# LoRaGN.net
KiCad netlist of a schematic drawn in Altium Designer
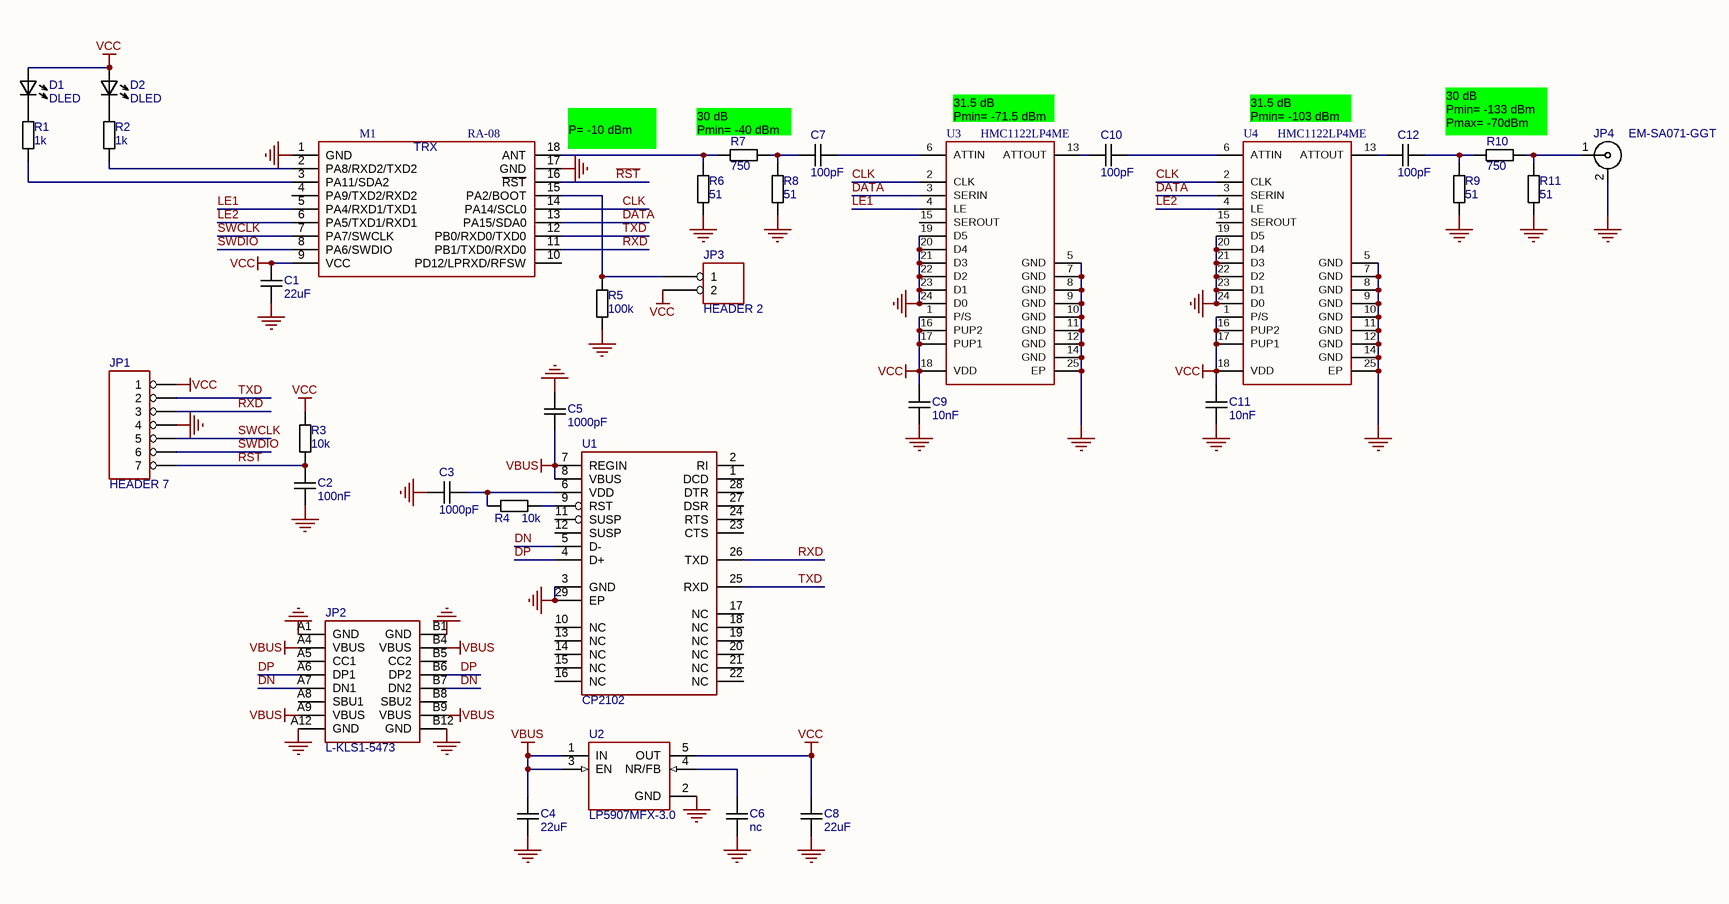
[diagram p0: LoRaGN.SchDoc]

(export (version "E")
  (design (tool "Eeschema 10.0.6"))
  (components
    (comp (ref "C1")
      (value "22uF")
      (footprint "C-0805")
      (fields (field (name "VOLTAGE") "50V"))
      (libsource (lib "Passive") (part "CAPN"))
    )
    (comp (ref "C2")
      (value "100nF")
      (footprint "C-0603")
      (fields (field (name "VOLTAGE") "50V"))
      (libsource (lib "Passive") (part "CAPN"))
    )
    (comp (ref "C3")
      (value "1000pF")
      (footprint "C-0603")
      (fields (field (name "VOLTAGE") "50V"))
      (libsource (lib "Passive") (part "CAPN"))
    )
    (comp (ref "C4")
      (value "22uF")
      (footprint "C-0805")
      (fields (field (name "VOLTAGE") "50V"))
      (libsource (lib "Passive") (part "CAPN"))
    )
    (comp (ref "C5")
      (value "1000pF")
      (footprint "C-0603")
      (fields (field (name "VOLTAGE") "50V"))
      (libsource (lib "Passive") (part "CAPN"))
    )
    (comp (ref "C6")
      (value "nc")
      (footprint "C-0603")
      (fields (field (name "VOLTAGE") "50V"))
      (libsource (lib "Passive") (part "CAPN"))
    )
    (comp (ref "C7")
      (value "100pF")
      (footprint "C-0603")
      (fields (field (name "VOLTAGE") "50V"))
      (libsource (lib "Passive") (part "CAPN"))
    )
    (comp (ref "C8")
      (value "22uF")
      (footprint "C-0805")
      (fields (field (name "VOLTAGE") "50V"))
      (libsource (lib "Passive") (part "CAPN"))
    )
    (comp (ref "C9")
      (value "10nF")
      (footprint "C-0603")
      (fields (field (name "VOLTAGE") "50V"))
      (libsource (lib "Passive") (part "CAPN"))
    )
    (comp (ref "C10")
      (value "100pF")
      (footprint "C-0603")
      (fields (field (name "VOLTAGE") "50V"))
      (libsource (lib "Passive") (part "CAPN"))
    )
    (comp (ref "C11")
      (value "10nF")
      (footprint "C-0603")
      (fields (field (name "VOLTAGE") "50V"))
      (libsource (lib "Passive") (part "CAPN"))
    )
    (comp (ref "C12")
      (value "100pF")
      (footprint "C-0603")
      (fields (field (name "VOLTAGE") "50V"))
      (libsource (lib "Passive") (part "CAPN"))
    )
    (comp (ref "D1") (value "DLED") (footprint "LED0805") (libsource (lib "Diodes") (part "DLED")))
    (comp (ref "D2") (value "DLED") (footprint "LED0805") (libsource (lib "Diodes") (part "DLED")))
    (comp (ref "JP1")
      (value "HEADER 7")
      (footprint "PLS1-7")
      (libsource (lib "Connectors") (part "HEADER 7"))
    )
    (comp (ref "JP2")
      (value "L-KLS1-5473")
      (footprint "L-KLS1-5473")
      (libsource (lib "Connectors") (part "L-KLS1-5473"))
    )
    (comp (ref "JP3")
      (value "HEADER 2")
      (footprint "PLS1-2")
      (libsource (lib "Connectors") (part "HEADER 2"))
    )
    (comp (ref "JP4")
      (value "EM-SA071-GGT")
      (footprint "SMA_F_EDGE")
      (description "SMA Female R/A PCB Mount")
      (libsource (lib "Connectors") (part "SMA"))
    )
    (comp (ref "M1") (value "RA-08") (footprint "LGA18_RA08") (libsource (lib "RFmodules") (part "RA-08")))
    (comp (ref "R1") (value "1k") (footprint "R-0603") (libsource (lib "Passive") (part "RES")))
    (comp (ref "R2") (value "1k") (footprint "R-0603") (libsource (lib "Passive") (part "RES")))
    (comp (ref "R3") (value "10k") (footprint "R-0603") (libsource (lib "Passive") (part "RES")))
    (comp (ref "R4") (value "10k") (footprint "R-0603") (libsource (lib "") (part "RES_1")))
    (comp (ref "R5") (value "100k") (footprint "R-0603") (libsource (lib "Passive") (part "RES")))
    (comp (ref "R6") (value "51") (footprint "R-0603") (libsource (lib "Passive") (part "RES")))
    (comp (ref "R7") (value "750") (footprint "R-0603") (libsource (lib "") (part "RES_2")))
    (comp (ref "R8") (value "51") (footprint "R-0603") (libsource (lib "Passive") (part "RES")))
    (comp (ref "R9") (value "51") (footprint "R-0603") (libsource (lib "Passive") (part "RES")))
    (comp (ref "R10") (value "750") (footprint "R-0603") (libsource (lib "") (part "RES_2")))
    (comp (ref "R11") (value "51") (footprint "R-0603") (libsource (lib "Passive") (part "RES")))
    (comp (ref "U1") (value "CP2102") (footprint "QFN28") (libsource (lib "ICs") (part "CP2102")))
    (comp (ref "U2")
      (value "LP5907MFX-3.0")
      (footprint "SOT-23-5")
      (description "250mA Low-Dropout Regulator")
      (libsource (lib "ICs") (part "LP5907"))
    )
    (comp (ref "U3")
      (value "HMC1122LP4ME")
      (footprint "QFN-24(4X4)")
      (libsource (lib "ICs") (part "HMC1122"))
    )
    (comp (ref "U4")
      (value "HMC1122LP4ME")
      (footprint "QFN-24(4X4)")
      (libsource (lib "ICs") (part "HMC1122"))
    )
  )
  (nets
    (net (code "1") (name "/CLK") (class "Default")
      (node (ref "M1") (pin "14") (pinfunction "PA14/SCL0_14") (pintype "passive"))
      (node (ref "U3") (pin "2") (pinfunction "CLK_2") (pintype "passive"))
      (node (ref "U4") (pin "2") (pinfunction "CLK_2") (pintype "passive"))
    )
    (net (code "2") (name "/DATA") (class "Default")
      (node (ref "M1") (pin "13") (pinfunction "PA15/SDA0_13") (pintype "passive"))
      (node (ref "U3") (pin "3") (pinfunction "SERIN_3") (pintype "passive"))
      (node (ref "U4") (pin "3") (pinfunction "SERIN_3") (pintype "passive"))
    )
    (net (code "3") (name "/DN") (class "Default")
      (node (ref "JP2") (pin "A7") (pinfunction "DN1_A7") (pintype "passive"))
      (node (ref "JP2") (pin "B7") (pinfunction "DN2_B7") (pintype "passive"))
      (node (ref "U1") (pin "5") (pinfunction "D-_5") (pintype "passive"))
    )
    (net (code "4") (name "/DP") (class "Default")
      (node (ref "JP2") (pin "A6") (pinfunction "DP1_A6") (pintype "passive"))
      (node (ref "JP2") (pin "B6") (pinfunction "DP2_B6") (pintype "passive"))
      (node (ref "U1") (pin "4") (pinfunction "D+_4") (pintype "passive"))
    )
    (net (code "5") (name "/LE1") (class "Default")
      (node (ref "M1") (pin "5") (pinfunction "PA4/RXD1/TXD1_5") (pintype "passive"))
      (node (ref "U3") (pin "4") (pinfunction "LE_4") (pintype "passive"))
    )
    (net (code "6") (name "/LE2") (class "Default")
      (node (ref "M1") (pin "6") (pinfunction "PA5/TXD1/RXD1_6") (pintype "passive"))
      (node (ref "U4") (pin "4") (pinfunction "LE_4") (pintype "passive"))
    )
    (net (code "7") (name "/RXD") (class "Default")
      (node (ref "JP1") (pin "3") (pinfunction "3_3") (pintype "passive"))
      (node (ref "M1") (pin "11") (pinfunction "PB1/TXD0/RXD0_11") (pintype "passive"))
      (node (ref "U1") (pin "26") (pinfunction "TXD_26") (pintype "passive"))
    )
    (net (code "8") (name "/SWCLK") (class "Default")
      (node (ref "JP1") (pin "5") (pinfunction "5_5") (pintype "passive"))
      (node (ref "M1") (pin "7") (pinfunction "PA7/SWCLK_7") (pintype "passive"))
    )
    (net (code "9") (name "/SWDIO") (class "Default")
      (node (ref "JP1") (pin "6") (pinfunction "6_6") (pintype "passive"))
      (node (ref "M1") (pin "8") (pinfunction "PA6/SWDIO_8") (pintype "passive"))
    )
    (net (code "10") (name "/TXD") (class "Default")
      (node (ref "JP1") (pin "2") (pinfunction "2_2") (pintype "passive"))
      (node (ref "M1") (pin "12") (pinfunction "PB0/RXD0/TXD0_12") (pintype "passive"))
      (node (ref "U1") (pin "25") (pinfunction "RXD_25") (pintype "passive"))
    )
    (net (code "11") (name "/~{RST}") (class "Default")
      (node (ref "C2") (pin "2") (pinfunction "2_2") (pintype "passive"))
      (node (ref "JP1") (pin "7") (pinfunction "7_7") (pintype "passive"))
      (node (ref "M1") (pin "16") (pinfunction "~{RST}_16") (pintype "passive"))
      (node (ref "R3") (pin "1") (pinfunction "1_1") (pintype "passive"))
    )
    (net (code "12") (name "GND") (class "Default")
      (node (ref "C1") (pin "1") (pinfunction "1_1") (pintype "passive"))
      (node (ref "C11") (pin "1") (pinfunction "1_1") (pintype "passive"))
      (node (ref "C2") (pin "1") (pinfunction "1_1") (pintype "passive"))
      (node (ref "C3") (pin "2") (pinfunction "2_2") (pintype "passive"))
      (node (ref "C4") (pin "2") (pinfunction "2_2") (pintype "passive"))
      (node (ref "C5") (pin "1") (pinfunction "1_1") (pintype "passive"))
      (node (ref "C6") (pin "2") (pinfunction "2_2") (pintype "passive"))
      (node (ref "C8") (pin "2") (pinfunction "2_2") (pintype "passive"))
      (node (ref "C9") (pin "1") (pinfunction "1_1") (pintype "passive"))
      (node (ref "JP1") (pin "4") (pinfunction "4_4") (pintype "passive"))
      (node (ref "JP2") (pin "A1") (pinfunction "GND_A1") (pintype "passive"))
      (node (ref "JP2") (pin "A12") (pinfunction "GND_A12") (pintype "passive"))
      (node (ref "JP2") (pin "B1") (pinfunction "GND_B1") (pintype "passive"))
      (node (ref "JP2") (pin "B12") (pinfunction "GND_B12") (pintype "passive"))
      (node (ref "JP4") (pin "2") (pinfunction "2_2") (pintype "passive"))
      (node (ref "M1") (pin "1") (pinfunction "GND_1") (pintype "passive"))
      (node (ref "M1") (pin "17") (pinfunction "GND_17") (pintype "passive"))
      (node (ref "R11") (pin "1") (pinfunction "1_1") (pintype "passive"))
      (node (ref "R5") (pin "1") (pinfunction "1_1") (pintype "passive"))
      (node (ref "R6") (pin "1") (pinfunction "1_1") (pintype "passive"))
      (node (ref "R8") (pin "1") (pinfunction "1_1") (pintype "passive"))
      (node (ref "R9") (pin "1") (pinfunction "1_1") (pintype "passive"))
      (node (ref "U1") (pin "29") (pinfunction "EP_29") (pintype "passive"))
      (node (ref "U1") (pin "3") (pinfunction "GND_3") (pintype "passive"))
      (node (ref "U2") (pin "2") (pinfunction "GND_2") (pintype "power_in"))
      (node (ref "U3") (pin "10") (pinfunction "GND_10") (pintype "passive"))
      (node (ref "U3") (pin "11") (pinfunction "GND_11") (pintype "passive"))
      (node (ref "U3") (pin "12") (pinfunction "GND_12") (pintype "passive"))
      (node (ref "U3") (pin "14") (pinfunction "GND_14") (pintype "passive"))
      (node (ref "U3") (pin "19") (pinfunction "D5_19") (pintype "passive"))
      (node (ref "U3") (pin "20") (pinfunction "D4_20") (pintype "passive"))
      (node (ref "U3") (pin "21") (pinfunction "D3_21") (pintype "passive"))
      (node (ref "U3") (pin "22") (pinfunction "D2_22") (pintype "passive"))
      (node (ref "U3") (pin "23") (pinfunction "D1_23") (pintype "passive"))
      (node (ref "U3") (pin "24") (pinfunction "D0_24") (pintype "passive"))
      (node (ref "U3") (pin "25") (pinfunction "EP_25") (pintype "passive"))
      (node (ref "U3") (pin "5") (pinfunction "GND_5") (pintype "passive"))
      (node (ref "U3") (pin "7") (pinfunction "GND_7") (pintype "passive"))
      (node (ref "U3") (pin "8") (pinfunction "GND_8") (pintype "passive"))
      (node (ref "U3") (pin "9") (pinfunction "GND_9") (pintype "passive"))
      (node (ref "U4") (pin "10") (pinfunction "GND_10") (pintype "passive"))
      (node (ref "U4") (pin "11") (pinfunction "GND_11") (pintype "passive"))
      (node (ref "U4") (pin "12") (pinfunction "GND_12") (pintype "passive"))
      (node (ref "U4") (pin "14") (pinfunction "GND_14") (pintype "passive"))
      (node (ref "U4") (pin "19") (pinfunction "D5_19") (pintype "passive"))
      (node (ref "U4") (pin "20") (pinfunction "D4_20") (pintype "passive"))
      (node (ref "U4") (pin "21") (pinfunction "D3_21") (pintype "passive"))
      (node (ref "U4") (pin "22") (pinfunction "D2_22") (pintype "passive"))
      (node (ref "U4") (pin "23") (pinfunction "D1_23") (pintype "passive"))
      (node (ref "U4") (pin "24") (pinfunction "D0_24") (pintype "passive"))
      (node (ref "U4") (pin "25") (pinfunction "EP_25") (pintype "passive"))
      (node (ref "U4") (pin "5") (pinfunction "GND_5") (pintype "passive"))
      (node (ref "U4") (pin "7") (pinfunction "GND_7") (pintype "passive"))
      (node (ref "U4") (pin "8") (pinfunction "GND_8") (pintype "passive"))
      (node (ref "U4") (pin "9") (pinfunction "GND_9") (pintype "passive"))
    )
    (net (code "13") (name "Net-(C7-Pad1)") (class "Default")
      (node (ref "C7") (pin "1") (pinfunction "1_1") (pintype "passive"))
      (node (ref "R7") (pin "2") (pinfunction "2_2") (pintype "passive"))
      (node (ref "R8") (pin "2") (pinfunction "2_2") (pintype "passive"))
    )
    (net (code "14") (name "Net-(C12-Pad2)") (class "Default")
      (node (ref "C12") (pin "2") (pinfunction "2_2") (pintype "passive"))
      (node (ref "R10") (pin "1") (pinfunction "1_1") (pintype "passive"))
      (node (ref "R9") (pin "2") (pinfunction "2_2") (pintype "passive"))
    )
    (net (code "15") (name "Net-(D1-Pad2)") (class "Default")
      (node (ref "D1") (pin "2") (pinfunction "2_2") (pintype "passive"))
      (node (ref "R1") (pin "2") (pinfunction "2_2") (pintype "passive"))
    )
    (net (code "16") (name "Net-(D2-Pad2)") (class "Default")
      (node (ref "D2") (pin "2") (pinfunction "2_2") (pintype "passive"))
      (node (ref "R2") (pin "2") (pinfunction "2_2") (pintype "passive"))
    )
    (net (code "17") (name "Net-(JP4-Pad1)") (class "Default")
      (node (ref "JP4") (pin "1") (pinfunction "1_1") (pintype "passive"))
      (node (ref "R10") (pin "2") (pinfunction "2_2") (pintype "passive"))
      (node (ref "R11") (pin "2") (pinfunction "2_2") (pintype "passive"))
    )
    (net (code "18") (name "Net-(M1-ANT)") (class "Default")
      (node (ref "M1") (pin "18") (pinfunction "ANT_18") (pintype "passive"))
      (node (ref "R6") (pin "2") (pinfunction "2_2") (pintype "passive"))
      (node (ref "R7") (pin "1") (pinfunction "1_1") (pintype "passive"))
    )
    (net (code "19") (name "Net-(M1-PA2{slash}BOOT)") (class "Default")
      (node (ref "JP3") (pin "1") (pinfunction "1_1") (pintype "passive"))
      (node (ref "M1") (pin "15") (pinfunction "PA2/BOOT_15") (pintype "passive"))
      (node (ref "R5") (pin "2") (pinfunction "2_2") (pintype "passive"))
    )
    (net (code "20") (name "Net-(M1-PA8{slash}RXD2{slash}TXD2)") (class "Default")
      (node (ref "M1") (pin "2") (pinfunction "PA8/RXD2/TXD2_2") (pintype "passive"))
      (node (ref "R2") (pin "1") (pinfunction "1_1") (pintype "passive"))
    )
    (net (code "21") (name "Net-(M1-PA11{slash}SDA2)") (class "Default")
      (node (ref "M1") (pin "3") (pinfunction "PA11/SDA2_3") (pintype "passive"))
      (node (ref "R1") (pin "1") (pinfunction "1_1") (pintype "passive"))
    )
    (net (code "22") (name "Net-(U1-RST)") (class "Default")
      (node (ref "R4") (pin "1") (pinfunction "1_1") (pintype "passive"))
      (node (ref "U1") (pin "9") (pinfunction "RST_9") (pintype "passive"))
    )
    (net (code "23") (name "Net-(U1-VDD)") (class "Default")
      (node (ref "C3") (pin "1") (pinfunction "1_1") (pintype "passive"))
      (node (ref "R4") (pin "2") (pinfunction "2_2") (pintype "passive"))
      (node (ref "U1") (pin "6") (pinfunction "VDD_6") (pintype "passive"))
    )
    (net (code "24") (name "Net-(U2-NR{slash}FB)") (class "Default")
      (node (ref "C6") (pin "1") (pinfunction "1_1") (pintype "passive"))
      (node (ref "U2") (pin "4") (pinfunction "NR/FB_4") (pintype "input"))
    )
    (net (code "25") (name "Net-(U3-ATTIN)") (class "Default")
      (node (ref "C7") (pin "2") (pinfunction "2_2") (pintype "passive"))
      (node (ref "U3") (pin "6") (pinfunction "ATTIN_6") (pintype "passive"))
    )
    (net (code "26") (name "Net-(U3-ATTOUT)") (class "Default")
      (node (ref "C10") (pin "1") (pinfunction "1_1") (pintype "passive"))
      (node (ref "U3") (pin "13") (pinfunction "ATTOUT_13") (pintype "passive"))
    )
    (net (code "27") (name "Net-(U4-ATTIN)") (class "Default")
      (node (ref "C10") (pin "2") (pinfunction "2_2") (pintype "passive"))
      (node (ref "U4") (pin "6") (pinfunction "ATTIN_6") (pintype "passive"))
    )
    (net (code "28") (name "Net-(U4-ATTOUT)") (class "Default")
      (node (ref "C12") (pin "1") (pinfunction "1_1") (pintype "passive"))
      (node (ref "U4") (pin "13") (pinfunction "ATTOUT_13") (pintype "passive"))
    )
    (net (code "29") (name "VBUS") (class "Default")
      (node (ref "C4") (pin "1") (pinfunction "1_1") (pintype "passive"))
      (node (ref "C5") (pin "2") (pinfunction "2_2") (pintype "passive"))
      (node (ref "JP2") (pin "A4") (pinfunction "VBUS_A4") (pintype "passive"))
      (node (ref "JP2") (pin "A9") (pinfunction "VBUS_A9") (pintype "passive"))
      (node (ref "JP2") (pin "B4") (pinfunction "VBUS_B4") (pintype "passive"))
      (node (ref "JP2") (pin "B9") (pinfunction "VBUS_B9") (pintype "passive"))
      (node (ref "U1") (pin "7") (pinfunction "REGIN_7") (pintype "passive"))
      (node (ref "U1") (pin "8") (pinfunction "VBUS_8") (pintype "passive"))
      (node (ref "U2") (pin "1") (pinfunction "IN_1") (pintype "power_in"))
      (node (ref "U2") (pin "3") (pinfunction "EN_3") (pintype "input"))
    )
    (net (code "30") (name "VCC") (class "Default")
      (node (ref "C1") (pin "2") (pinfunction "2_2") (pintype "passive"))
      (node (ref "C11") (pin "2") (pinfunction "2_2") (pintype "passive"))
      (node (ref "C8") (pin "1") (pinfunction "1_1") (pintype "passive"))
      (node (ref "C9") (pin "2") (pinfunction "2_2") (pintype "passive"))
      (node (ref "D1") (pin "1") (pinfunction "1_1") (pintype "passive"))
      (node (ref "D2") (pin "1") (pinfunction "1_1") (pintype "passive"))
      (node (ref "JP1") (pin "1") (pinfunction "1_1") (pintype "passive"))
      (node (ref "JP3") (pin "2") (pinfunction "2_2") (pintype "passive"))
      (node (ref "M1") (pin "9") (pinfunction "VCC_9") (pintype "passive"))
      (node (ref "R3") (pin "2") (pinfunction "2_2") (pintype "passive"))
      (node (ref "U2") (pin "5") (pinfunction "OUT_5") (pintype "power_in"))
      (node (ref "U3") (pin "1") (pinfunction "P/S_1") (pintype "passive"))
      (node (ref "U3") (pin "16") (pinfunction "PUP2_16") (pintype "passive"))
      (node (ref "U3") (pin "17") (pinfunction "PUP1_17") (pintype "passive"))
      (node (ref "U3") (pin "18") (pinfunction "VDD_18") (pintype "passive"))
      (node (ref "U4") (pin "1") (pinfunction "P/S_1") (pintype "passive"))
      (node (ref "U4") (pin "16") (pinfunction "PUP2_16") (pintype "passive"))
      (node (ref "U4") (pin "17") (pinfunction "PUP1_17") (pintype "passive"))
      (node (ref "U4") (pin "18") (pinfunction "VDD_18") (pintype "passive"))
    )
    (net (code "31") (name "VSS") (class "Default")
      (node (ref "JP2") (pin "17") (pinfunction "VSS_17") (pintype "power_in"))
    )
    (net (code "32") (name "unconnected-(JP2-CC1-PadA5)") (class "Default")
      (node (ref "JP2") (pin "A5") (pinfunction "CC1_A5") (pintype "passive"))
    )
    (net (code "33") (name "unconnected-(JP2-CC2-PadB5)") (class "Default")
      (node (ref "JP2") (pin "B5") (pinfunction "CC2_B5") (pintype "passive"))
    )
    (net (code "34") (name "unconnected-(JP2-SBU1-PadA8)") (class "Default")
      (node (ref "JP2") (pin "A8") (pinfunction "SBU1_A8") (pintype "passive"))
    )
    (net (code "35") (name "unconnected-(JP2-SBU2-PadB8)") (class "Default")
      (node (ref "JP2") (pin "B8") (pinfunction "SBU2_B8") (pintype "passive"))
    )
    (net (code "36") (name "unconnected-(M1-PA9{slash}TXD2{slash}RXD2-Pad4)") (class "Default")
      (node (ref "M1") (pin "4") (pinfunction "PA9/TXD2/RXD2_4") (pintype "passive"))
    )
    (net (code "37") (name "unconnected-(M1-PD12{slash}LPRXD{slash}RFSW-Pad10)") (class "Default")
      (node (ref "M1") (pin "10") (pinfunction "PD12/LPRXD/RFSW_10") (pintype "passive"))
    )
    (net (code "38") (name "unconnected-(U1-CTS-Pad23)") (class "Default")
      (node (ref "U1") (pin "23") (pinfunction "CTS_23") (pintype "passive"))
    )
    (net (code "39") (name "unconnected-(U1-DCD-Pad1)") (class "Default")
      (node (ref "U1") (pin "1") (pinfunction "DCD_1") (pintype "passive"))
    )
    (net (code "40") (name "unconnected-(U1-DSR-Pad27)") (class "Default")
      (node (ref "U1") (pin "27") (pinfunction "DSR_27") (pintype "passive"))
    )
    (net (code "41") (name "unconnected-(U1-DTR-Pad28)") (class "Default")
      (node (ref "U1") (pin "28") (pinfunction "DTR_28") (pintype "passive"))
    )
    (net (code "42") (name "unconnected-(U1-NC-Pad10)") (class "Default")
      (node (ref "U1") (pin "10") (pinfunction "NC_10") (pintype "passive"))
    )
    (net (code "43") (name "unconnected-(U1-NC-Pad13)") (class "Default")
      (node (ref "U1") (pin "13") (pinfunction "NC_13") (pintype "passive"))
    )
    (net (code "44") (name "unconnected-(U1-NC-Pad14)") (class "Default")
      (node (ref "U1") (pin "14") (pinfunction "NC_14") (pintype "passive"))
    )
    (net (code "45") (name "unconnected-(U1-NC-Pad15)") (class "Default")
      (node (ref "U1") (pin "15") (pinfunction "NC_15") (pintype "passive"))
    )
    (net (code "46") (name "unconnected-(U1-NC-Pad16)") (class "Default")
      (node (ref "U1") (pin "16") (pinfunction "NC_16") (pintype "passive"))
    )
    (net (code "47") (name "unconnected-(U1-NC-Pad17)") (class "Default")
      (node (ref "U1") (pin "17") (pinfunction "NC_17") (pintype "passive"))
    )
    (net (code "48") (name "unconnected-(U1-NC-Pad18)") (class "Default")
      (node (ref "U1") (pin "18") (pinfunction "NC_18") (pintype "passive"))
    )
    (net (code "49") (name "unconnected-(U1-NC-Pad19)") (class "Default")
      (node (ref "U1") (pin "19") (pinfunction "NC_19") (pintype "passive"))
    )
    (net (code "50") (name "unconnected-(U1-NC-Pad20)") (class "Default")
      (node (ref "U1") (pin "20") (pinfunction "NC_20") (pintype "passive"))
    )
    (net (code "51") (name "unconnected-(U1-NC-Pad21)") (class "Default")
      (node (ref "U1") (pin "21") (pinfunction "NC_21") (pintype "passive"))
    )
    (net (code "52") (name "unconnected-(U1-NC-Pad22)") (class "Default")
      (node (ref "U1") (pin "22") (pinfunction "NC_22") (pintype "passive"))
    )
    (net (code "53") (name "unconnected-(U1-RI-Pad2)") (class "Default")
      (node (ref "U1") (pin "2") (pinfunction "RI_2") (pintype "passive"))
    )
    (net (code "54") (name "unconnected-(U1-RTS-Pad24)") (class "Default")
      (node (ref "U1") (pin "24") (pinfunction "RTS_24") (pintype "passive"))
    )
    (net (code "55") (name "unconnected-(U1-SUSP-Pad11)") (class "Default")
      (node (ref "U1") (pin "11") (pinfunction "SUSP_11") (pintype "passive"))
    )
    (net (code "56") (name "unconnected-(U1-SUSP-Pad12)") (class "Default")
      (node (ref "U1") (pin "12") (pinfunction "SUSP_12") (pintype "passive"))
    )
    (net (code "57") (name "unconnected-(U3-SEROUT-Pad15)") (class "Default")
      (node (ref "U3") (pin "15") (pinfunction "SEROUT_15") (pintype "passive"))
    )
    (net (code "58") (name "unconnected-(U4-SEROUT-Pad15)") (class "Default")
      (node (ref "U4") (pin "15") (pinfunction "SEROUT_15") (pintype "passive"))
    )
  )
)
